# FFC_Adapters_10.net
KiCad netlist of a schematic drawn in EAGLE
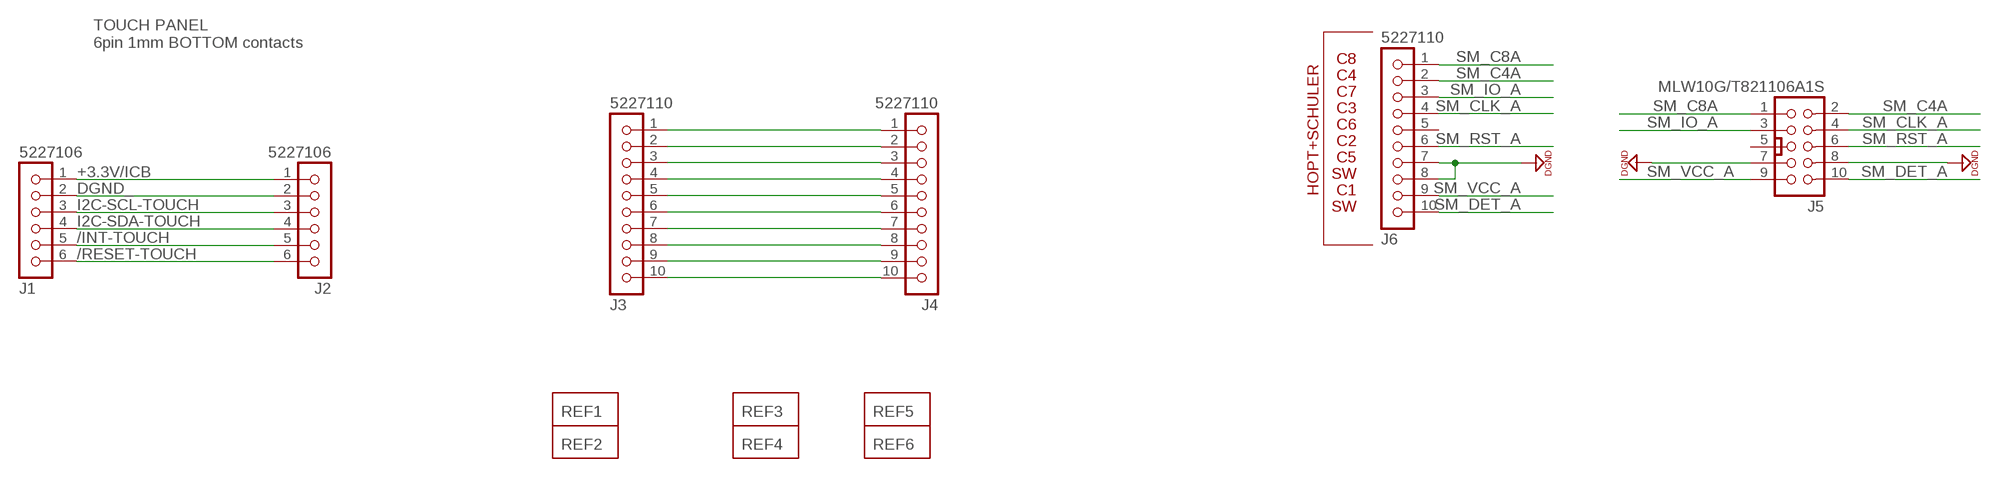
[diagram p0: schematic, sheet 1]

(export (version "E")
  (design (tool "Eeschema 10.0.6"))
  (components
    (comp (ref "J1")
      (value "5227106")
      (footprint "eagle-import:5227106_1.LEFT")
      (libsource (lib "eagle-import") (part "5227106/1.LEFT"))
    )
    (comp (ref "J2")
      (value "5227106")
      (footprint "eagle-import:5227106_1.RIGHT")
      (libsource (lib "eagle-import") (part "5227106/1.RIGHT"))
    )
    (comp (ref "J3")
      (value "5227110")
      (footprint "eagle-import:5227110_1.LEFT")
      (libsource (lib "eagle-import") (part "5227110/1.LEFT"))
    )
    (comp (ref "J4")
      (value "5227110")
      (footprint "eagle-import:5227110_1.RIGHT")
      (libsource (lib "eagle-import") (part "5227110/1.RIGHT"))
    )
    (comp (ref "J5")
      (value "MLW10G/T821106A1S")
      (footprint "eagle-import:MLW10-5X2-PRIMY")
      (libsource (lib "eagle-import") (part "MLW10G/T821106A1S"))
    )
    (comp (ref "J6")
      (value "5227110")
      (footprint "eagle-import:5227110_1.RIGHT")
      (libsource (lib "eagle-import") (part "5227110/1.RIGHT"))
    )
    (comp (ref "REF1")
      (value "REF")
      (footprint "eagle-import:REF")
      (libsource (lib "eagle-import") (part "REF"))
    )
    (comp (ref "REF2")
      (value "REF")
      (footprint "eagle-import:REF")
      (libsource (lib "eagle-import") (part "REF"))
    )
    (comp (ref "REF3")
      (value "REF")
      (footprint "eagle-import:REF")
      (libsource (lib "eagle-import") (part "REF"))
    )
    (comp (ref "REF4")
      (value "REF")
      (footprint "eagle-import:REF")
      (libsource (lib "eagle-import") (part "REF"))
    )
    (comp (ref "REF5")
      (value "REF")
      (footprint "eagle-import:REF")
      (libsource (lib "eagle-import") (part "REF"))
    )
    (comp (ref "REF6")
      (value "REF")
      (footprint "eagle-import:REF")
      (libsource (lib "eagle-import") (part "REF"))
    )
  )
  (nets
    (net (code "1") (name "/+3.3V{slash}ICB") (class "Default")
      (node (ref "J1") (pin "1") (pinfunction "1_1") (pintype "passive"))
      (node (ref "J2") (pin "1") (pinfunction "1_1") (pintype "passive"))
    )
    (net (code "2") (name "/DGND_") (class "Default")
      (node (ref "J1") (pin "2") (pinfunction "2_2") (pintype "passive"))
      (node (ref "J2") (pin "2") (pinfunction "2_2") (pintype "passive"))
    )
    (net (code "3") (name "/I2C-SCL-TOUCH") (class "Default")
      (node (ref "J1") (pin "3") (pinfunction "3_3") (pintype "passive"))
      (node (ref "J2") (pin "3") (pinfunction "3_3") (pintype "passive"))
    )
    (net (code "4") (name "/I2C-SDA-TOUCH") (class "Default")
      (node (ref "J1") (pin "4") (pinfunction "4_4") (pintype "passive"))
      (node (ref "J2") (pin "4") (pinfunction "4_4") (pintype "passive"))
    )
    (net (code "5") (name "/SM_C4A") (class "Default")
      (node (ref "J5") (pin "2") (pinfunction "2_2") (pintype "passive"))
      (node (ref "J6") (pin "2") (pinfunction "2_2") (pintype "passive"))
    )
    (net (code "6") (name "/SM_C8A") (class "Default")
      (node (ref "J5") (pin "1") (pinfunction "1_1") (pintype "passive"))
      (node (ref "J6") (pin "1") (pinfunction "1_1") (pintype "passive"))
    )
    (net (code "7") (name "/SM_CLK_A") (class "Default")
      (node (ref "J5") (pin "4") (pinfunction "4_4") (pintype "passive"))
      (node (ref "J6") (pin "4") (pinfunction "4_4") (pintype "passive"))
    )
    (net (code "8") (name "/SM_DET_A") (class "Default")
      (node (ref "J5") (pin "10") (pinfunction "10_10") (pintype "passive"))
      (node (ref "J6") (pin "10") (pinfunction "10_10") (pintype "passive"))
    )
    (net (code "9") (name "/SM_IO_A") (class "Default")
      (node (ref "J5") (pin "3") (pinfunction "3_3") (pintype "passive"))
      (node (ref "J6") (pin "3") (pinfunction "3_3") (pintype "passive"))
    )
    (net (code "10") (name "/SM_RST_A") (class "Default")
      (node (ref "J5") (pin "6") (pinfunction "6_6") (pintype "passive"))
      (node (ref "J6") (pin "6") (pinfunction "6_6") (pintype "passive"))
    )
    (net (code "11") (name "/SM_VCC_A") (class "Default")
      (node (ref "J5") (pin "9") (pinfunction "9_9") (pintype "passive"))
      (node (ref "J6") (pin "9") (pinfunction "9_9") (pintype "passive"))
    )
    (net (code "12") (name "/{slash}INT-TOUCH") (class "Default")
      (node (ref "J1") (pin "5") (pinfunction "5_5") (pintype "passive"))
      (node (ref "J2") (pin "5") (pinfunction "5_5") (pintype "passive"))
    )
    (net (code "13") (name "/{slash}RESET-TOUCH") (class "Default")
      (node (ref "J1") (pin "6") (pinfunction "6_6") (pintype "passive"))
      (node (ref "J2") (pin "6") (pinfunction "6_6") (pintype "passive"))
    )
    (net (code "14") (name "DGND") (class "Default")
      (node (ref "J5") (pin "7") (pinfunction "7_7") (pintype "passive"))
      (node (ref "J5") (pin "8") (pinfunction "8_8") (pintype "passive"))
      (node (ref "J6") (pin "7") (pinfunction "7_7") (pintype "passive"))
      (node (ref "J6") (pin "8") (pinfunction "8_8") (pintype "passive"))
    )
    (net (code "15") (name "Net-(J3-Pad1)") (class "Default")
      (node (ref "J3") (pin "1") (pinfunction "1_1") (pintype "passive"))
      (node (ref "J4") (pin "1") (pinfunction "1_1") (pintype "passive"))
    )
    (net (code "16") (name "Net-(J3-Pad2)") (class "Default")
      (node (ref "J3") (pin "2") (pinfunction "2_2") (pintype "passive"))
      (node (ref "J4") (pin "2") (pinfunction "2_2") (pintype "passive"))
    )
    (net (code "17") (name "Net-(J3-Pad3)") (class "Default")
      (node (ref "J3") (pin "3") (pinfunction "3_3") (pintype "passive"))
      (node (ref "J4") (pin "3") (pinfunction "3_3") (pintype "passive"))
    )
    (net (code "18") (name "Net-(J3-Pad4)") (class "Default")
      (node (ref "J3") (pin "4") (pinfunction "4_4") (pintype "passive"))
      (node (ref "J4") (pin "4") (pinfunction "4_4") (pintype "passive"))
    )
    (net (code "19") (name "Net-(J3-Pad5)") (class "Default")
      (node (ref "J3") (pin "5") (pinfunction "5_5") (pintype "passive"))
      (node (ref "J4") (pin "5") (pinfunction "5_5") (pintype "passive"))
    )
    (net (code "20") (name "Net-(J3-Pad6)") (class "Default")
      (node (ref "J3") (pin "6") (pinfunction "6_6") (pintype "passive"))
      (node (ref "J4") (pin "6") (pinfunction "6_6") (pintype "passive"))
    )
    (net (code "21") (name "Net-(J3-Pad7)") (class "Default")
      (node (ref "J3") (pin "7") (pinfunction "7_7") (pintype "passive"))
      (node (ref "J4") (pin "7") (pinfunction "7_7") (pintype "passive"))
    )
    (net (code "22") (name "Net-(J3-Pad8)") (class "Default")
      (node (ref "J3") (pin "8") (pinfunction "8_8") (pintype "passive"))
      (node (ref "J4") (pin "8") (pinfunction "8_8") (pintype "passive"))
    )
    (net (code "23") (name "Net-(J3-Pad9)") (class "Default")
      (node (ref "J3") (pin "9") (pinfunction "9_9") (pintype "passive"))
      (node (ref "J4") (pin "9") (pinfunction "9_9") (pintype "passive"))
    )
    (net (code "24") (name "Net-(J3-Pad10)") (class "Default")
      (node (ref "J3") (pin "10") (pinfunction "10_10") (pintype "passive"))
      (node (ref "J4") (pin "10") (pinfunction "10_10") (pintype "passive"))
    )
    (net (code "25") (name "unconnected-(J5-Pad5)") (class "Default")
      (node (ref "J5") (pin "5") (pinfunction "5_5") (pintype "passive"))
    )
    (net (code "26") (name "unconnected-(J6-Pad5)") (class "Default")
      (node (ref "J6") (pin "5") (pinfunction "5_5") (pintype "passive"))
    )
  )
)
